# AR-LCDONLY2.net
KiCad netlist of a schematic drawn in EAGLE
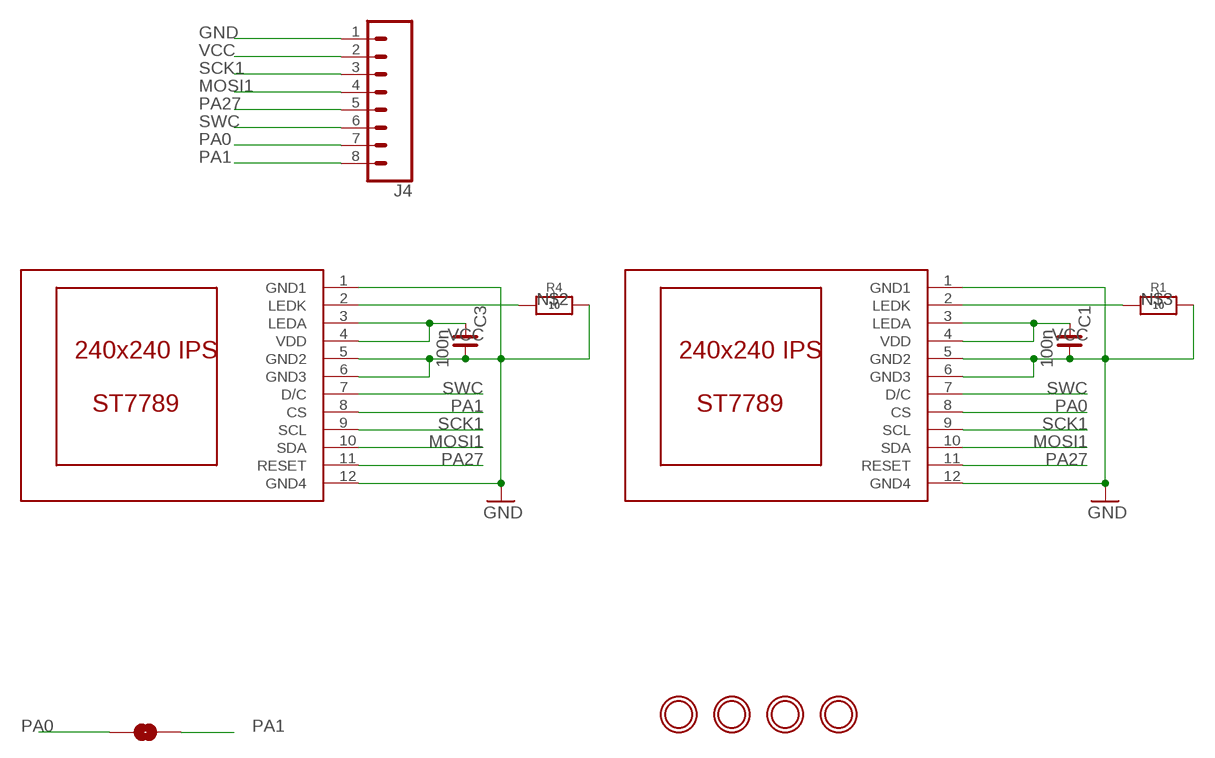
[diagram p0: schematic, sheet 1]

(export (version "E")
  (design (tool "Eeschema 10.0.6"))
  (components
    (comp (ref "C1")
      (value "100n")
      (footprint "eagle-import:C0805")
      (libsource (lib "eagle-import") (part "C_0805"))
    )
    (comp (ref "C3")
      (value "100n")
      (footprint "eagle-import:C0805")
      (libsource (lib "eagle-import") (part "C_0805"))
    )
    (comp (ref "J4")
      (value "CONN_08LONGPADS")
      (footprint "eagle-import:1X08_LONGPADS")
      (libsource (lib "eagle-import") (part "CONN_08LONGPADS"))
    )
    (comp (ref "JUMPER1")
      (value "SOLDERJUMPERNC2")
      (footprint "eagle-import:SJ_2S-NOTRACE")
      (libsource (lib "eagle-import") (part "SOLDERJUMPERNC2"))
    )
    (comp (ref "R1")
      (value "10")
      (footprint "eagle-import:_0805MP")
      (libsource (lib "eagle-import") (part "RESISTOR_0805MP"))
    )
    (comp (ref "R4")
      (value "10")
      (footprint "eagle-import:_0805MP")
      (libsource (lib "eagle-import") (part "RESISTOR_0805MP"))
    )
    (comp (ref "U$1")
      (value "DISP_LCD_0.9IN_160X80")
      (footprint "eagle-import:TFT_0.96IN_160X80")
      (libsource (lib "eagle-import") (part "DISP_LCD_0.9IN_160X80"))
    )
    (comp (ref "U$2")
      (value "MOUNTINGHOLE2.0")
      (footprint "eagle-import:MOUNTINGHOLE_2.0_PLATED")
      (libsource (lib "eagle-import") (part "MOUNTINGHOLE2.0"))
    )
    (comp (ref "U$3")
      (value "MOUNTINGHOLE2.0")
      (footprint "eagle-import:MOUNTINGHOLE_2.0_PLATED")
      (libsource (lib "eagle-import") (part "MOUNTINGHOLE2.0"))
    )
    (comp (ref "U$4")
      (value "MOUNTINGHOLE2.0")
      (footprint "eagle-import:MOUNTINGHOLE_2.0_PLATED")
      (libsource (lib "eagle-import") (part "MOUNTINGHOLE2.0"))
    )
    (comp (ref "U$10")
      (value "MOUNTINGHOLE2.0")
      (footprint "eagle-import:MOUNTINGHOLE_2.0_PLATED")
      (libsource (lib "eagle-import") (part "MOUNTINGHOLE2.0"))
    )
    (comp (ref "U$39")
      (value "DISP_LCD_0.9IN_160X80")
      (footprint "eagle-import:TFT_0.96IN_160X80")
      (libsource (lib "eagle-import") (part "DISP_LCD_0.9IN_160X80"))
    )
  )
  (nets
    (net (code "1") (name "/MOSI1") (class "Default")
      (node (ref "J4") (pin "4") (pinfunction "4_4") (pintype "passive"))
      (node (ref "U$1") (pin "10") (pinfunction "SDA_10") (pintype "power_in"))
      (node (ref "U$39") (pin "10") (pinfunction "SDA_10") (pintype "power_in"))
    )
    (net (code "2") (name "/N$2") (class "Default")
      (node (ref "R4") (pin "1") (pinfunction "1_1") (pintype "passive"))
      (node (ref "U$39") (pin "2") (pinfunction "LEDK_2") (pintype "input"))
    )
    (net (code "3") (name "/N$3") (class "Default")
      (node (ref "R1") (pin "1") (pinfunction "1_1") (pintype "passive"))
      (node (ref "U$1") (pin "2") (pinfunction "LEDK_2") (pintype "input"))
    )
    (net (code "4") (name "/PA0") (class "Default")
      (node (ref "J4") (pin "7") (pinfunction "7_7") (pintype "passive"))
      (node (ref "JUMPER1") (pin "2") (pinfunction "2_2") (pintype "passive"))
      (node (ref "U$1") (pin "8") (pinfunction "CS_8") (pintype "power_in"))
    )
    (net (code "5") (name "/PA1") (class "Default")
      (node (ref "J4") (pin "8") (pinfunction "8_8") (pintype "passive"))
      (node (ref "JUMPER1") (pin "1") (pinfunction "1_1") (pintype "passive"))
      (node (ref "U$39") (pin "8") (pinfunction "CS_8") (pintype "power_in"))
    )
    (net (code "6") (name "/PA27") (class "Default")
      (node (ref "J4") (pin "5") (pinfunction "5_5") (pintype "passive"))
      (node (ref "U$1") (pin "11") (pinfunction "RESET_11") (pintype "bidirectional"))
      (node (ref "U$39") (pin "11") (pinfunction "RESET_11") (pintype "bidirectional"))
    )
    (net (code "7") (name "/SCK1") (class "Default")
      (node (ref "J4") (pin "3") (pinfunction "3_3") (pintype "passive"))
      (node (ref "U$1") (pin "9") (pinfunction "SCL_9") (pintype "power_in"))
      (node (ref "U$39") (pin "9") (pinfunction "SCL_9") (pintype "power_in"))
    )
    (net (code "8") (name "/SWC") (class "Default")
      (node (ref "J4") (pin "6") (pinfunction "6_6") (pintype "passive"))
      (node (ref "U$1") (pin "7") (pinfunction "D/C_7") (pintype "input"))
      (node (ref "U$39") (pin "7") (pinfunction "D/C_7") (pintype "input"))
    )
    (net (code "9") (name "/VCC") (class "Default")
      (node (ref "C1") (pin "2") (pinfunction "2_2") (pintype "passive"))
      (node (ref "C3") (pin "2") (pinfunction "2_2") (pintype "passive"))
      (node (ref "J4") (pin "2") (pinfunction "2_2") (pintype "passive"))
      (node (ref "U$1") (pin "3") (pinfunction "LEDA_3") (pintype "input"))
      (node (ref "U$1") (pin "4") (pinfunction "VDD_4") (pintype "input"))
      (node (ref "U$39") (pin "3") (pinfunction "LEDA_3") (pintype "input"))
      (node (ref "U$39") (pin "4") (pinfunction "VDD_4") (pintype "input"))
    )
    (net (code "10") (name "GND") (class "Default")
      (node (ref "C1") (pin "1") (pinfunction "1_1") (pintype "passive"))
      (node (ref "C3") (pin "1") (pinfunction "1_1") (pintype "passive"))
      (node (ref "J4") (pin "1") (pinfunction "1_1") (pintype "passive"))
      (node (ref "R1") (pin "2") (pinfunction "2_2") (pintype "passive"))
      (node (ref "R4") (pin "2") (pinfunction "2_2") (pintype "passive"))
      (node (ref "U$1") (pin "1") (pinfunction "GND1_1") (pintype "input"))
      (node (ref "U$1") (pin "12") (pinfunction "GND4_12") (pintype "bidirectional"))
      (node (ref "U$1") (pin "5") (pinfunction "GND2_5") (pintype "bidirectional"))
      (node (ref "U$1") (pin "6") (pinfunction "GND3_6") (pintype "input"))
      (node (ref "U$39") (pin "1") (pinfunction "GND1_1") (pintype "input"))
      (node (ref "U$39") (pin "12") (pinfunction "GND4_12") (pintype "bidirectional"))
      (node (ref "U$39") (pin "5") (pinfunction "GND2_5") (pintype "bidirectional"))
      (node (ref "U$39") (pin "6") (pinfunction "GND3_6") (pintype "input"))
    )
  )
)
